# SCH__Atlas_2026-06-21.net
KiCad netlist of a schematic drawn in EasyEDA
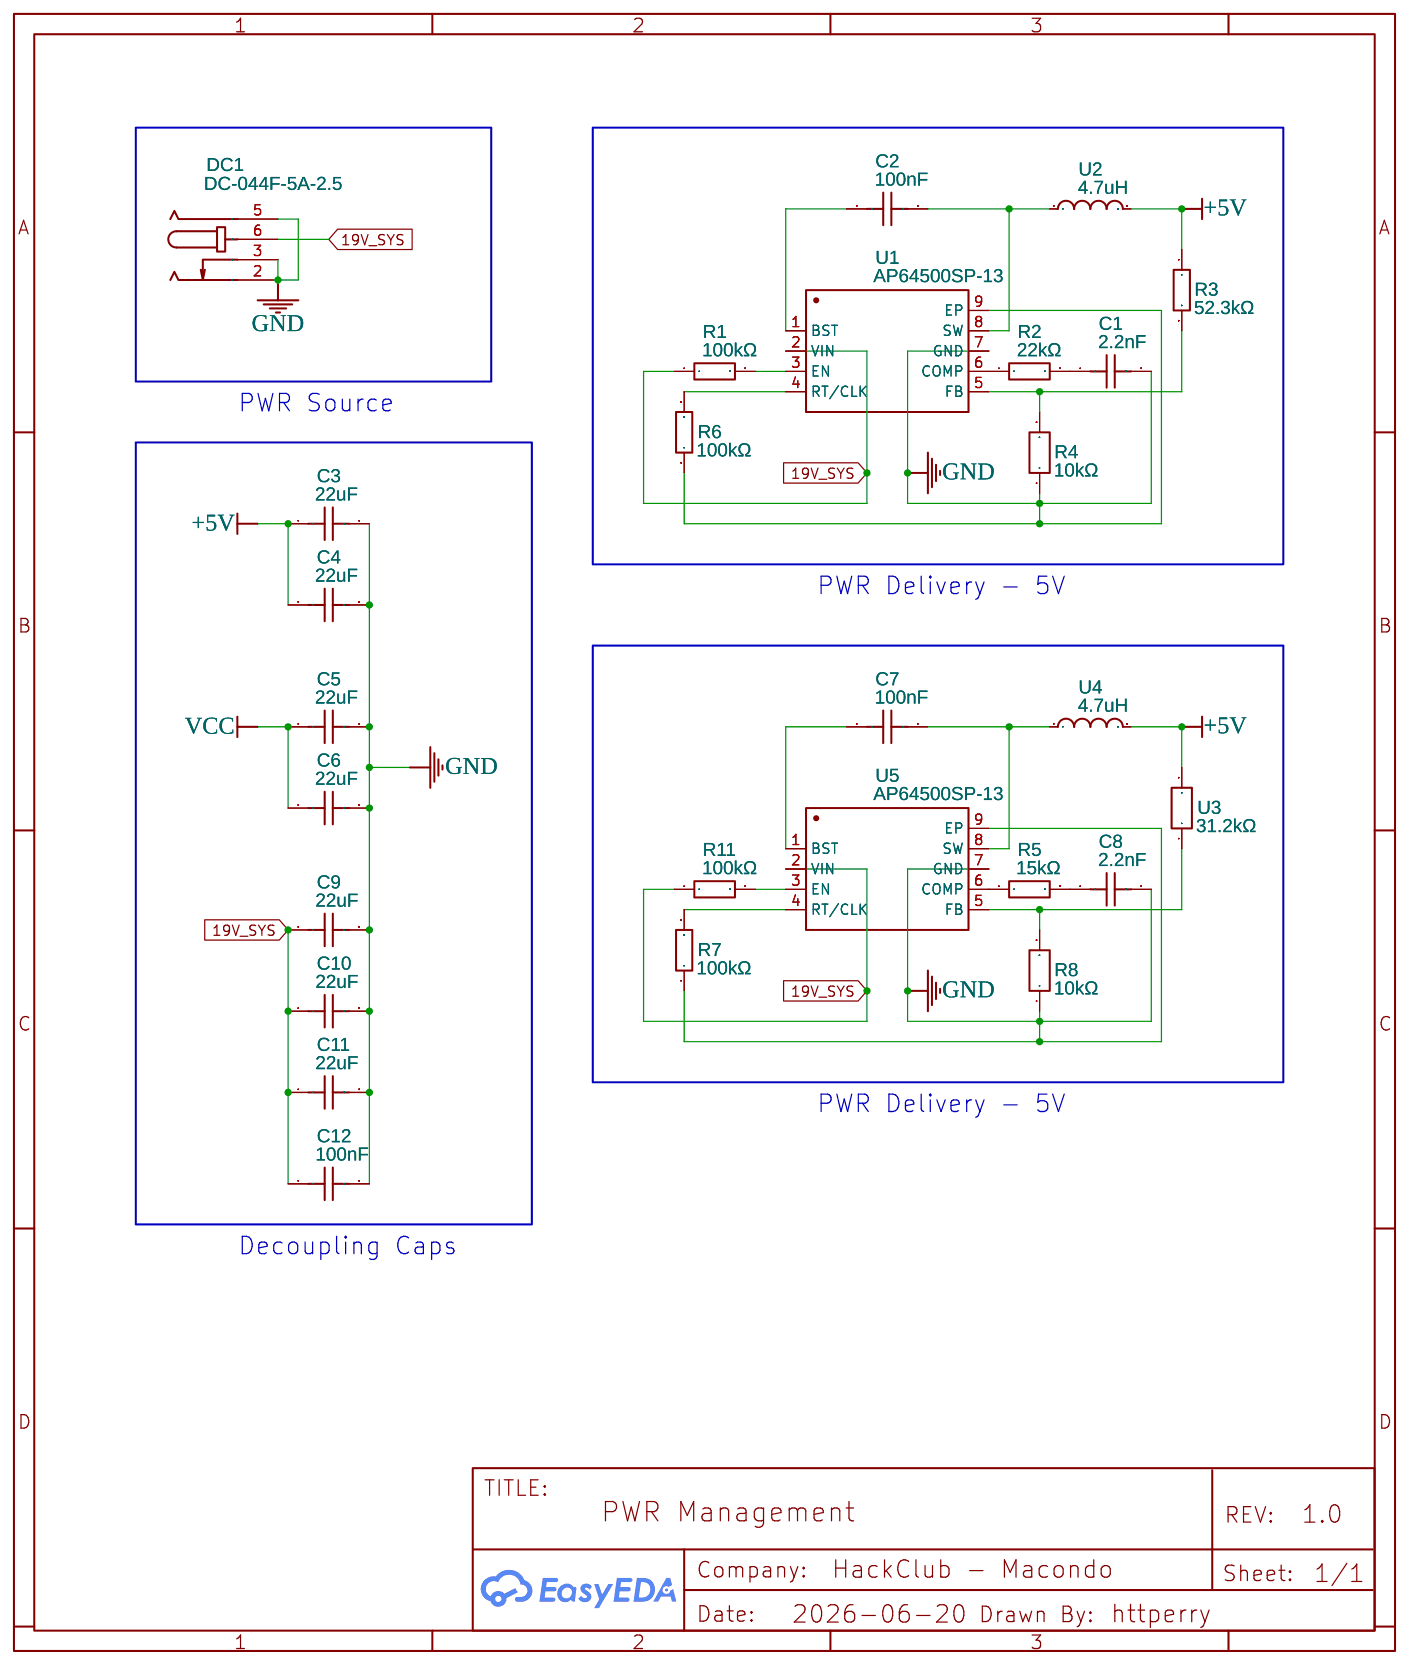
[diagram p0: PWR_Management]
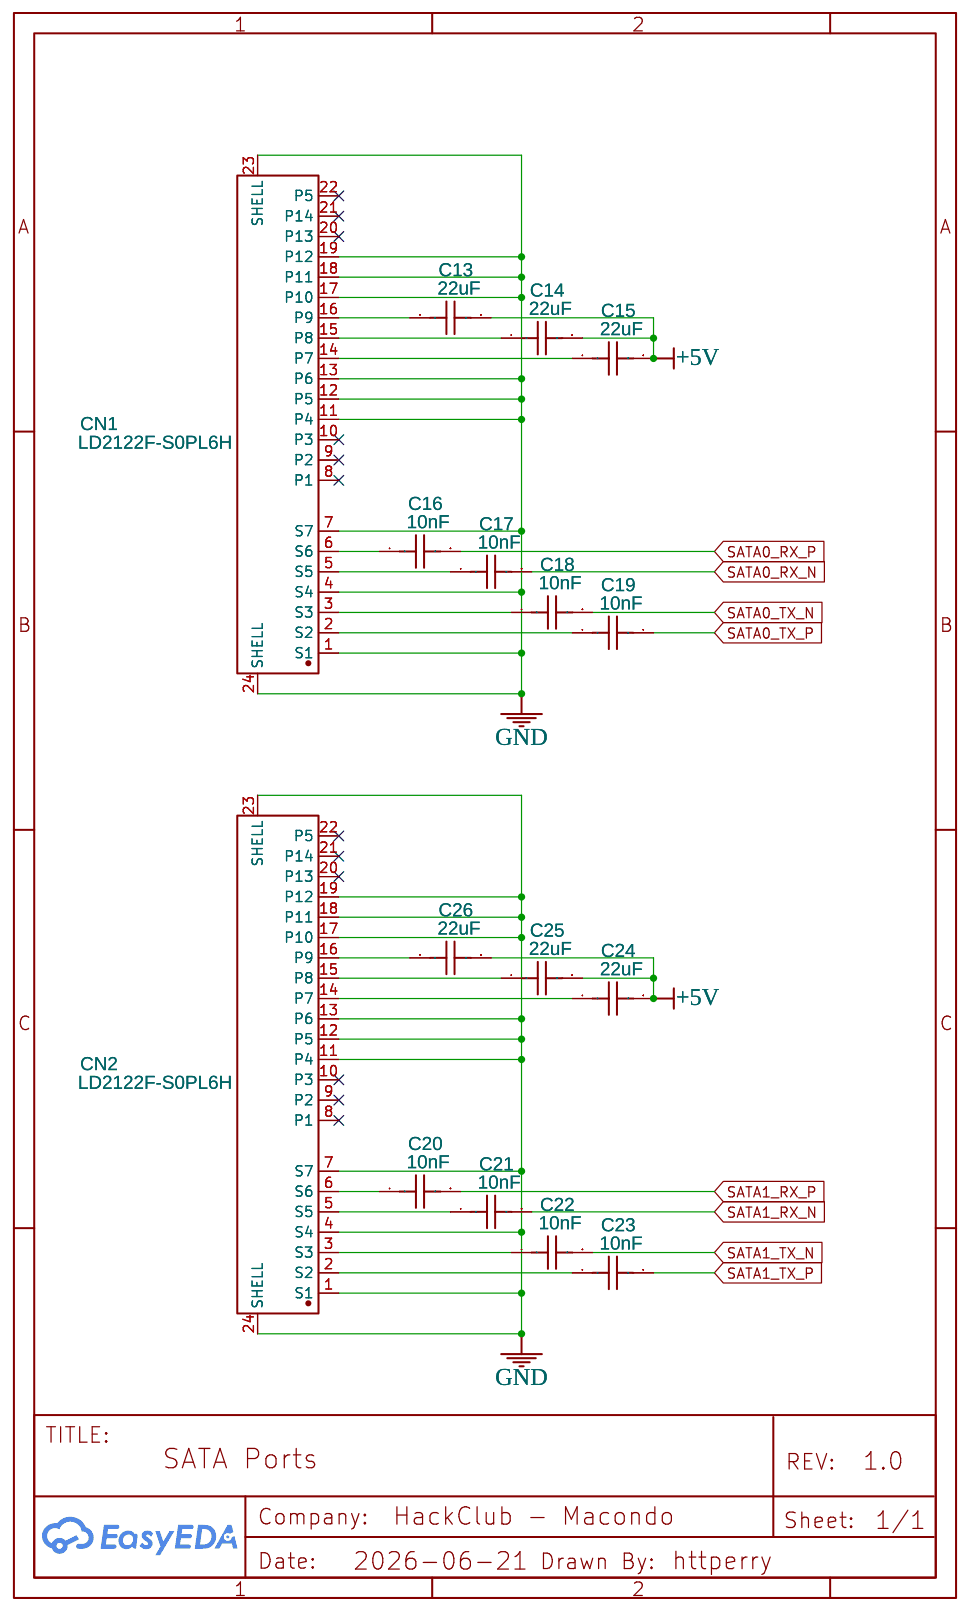
[diagram p1: SATA Ports]

(export (version "E")
  (design (tool "Eeschema 10.0.6"))
  (components
    (comp (ref "C1")
      (value "2.2nF")
      (fields
        (field (name "Manufacturer Part") "FCC0603B222K500CT")
        (field (name "Manufacturer") "FOJAN(富捷)")
      )
      (libsource (lib "") (part "FCC0603B222K500CT"))
    )
    (comp (ref "C2")
      (value "100nF")
      (fields
        (field (name "Manufacturer Part") "GRM188R71H104KA93D")
        (field (name "Manufacturer") "muRata(村田)")
      )
      (libsource (lib "") (part "GRM188R71H104KA93D"))
    )
    (comp (ref "C3")
      (value "22uF")
      (fields
        (field (name "Manufacturer Part") "HGC0603R5226M160NTHJ")
        (field (name "Manufacturer") "Chinocera(华瓷)")
      )
      (libsource (lib "") (part "HGC0603R5226M160NTHJ"))
    )
    (comp (ref "C4")
      (value "22uF")
      (fields
        (field (name "Manufacturer Part") "HGC0603R5226M160NTHJ")
        (field (name "Manufacturer") "Chinocera(华瓷)")
      )
      (libsource (lib "") (part "HGC0603R5226M160NTHJ"))
    )
    (comp (ref "C5")
      (value "22uF")
      (fields
        (field (name "Manufacturer Part") "HGC0603R5226M160NTHJ")
        (field (name "Manufacturer") "Chinocera(华瓷)")
      )
      (libsource (lib "") (part "HGC0603R5226M160NTHJ"))
    )
    (comp (ref "C6")
      (value "22uF")
      (fields
        (field (name "Manufacturer Part") "HGC0603R5226M160NTHJ")
        (field (name "Manufacturer") "Chinocera(华瓷)")
      )
      (libsource (lib "") (part "HGC0603R5226M160NTHJ"))
    )
    (comp (ref "C7")
      (value "100nF")
      (fields
        (field (name "Manufacturer Part") "GRM188R71H104KA93D")
        (field (name "Manufacturer") "muRata(村田)")
      )
      (libsource (lib "") (part "GRM188R71H104KA93D"))
    )
    (comp (ref "C8")
      (value "2.2nF")
      (fields
        (field (name "Manufacturer Part") "FCC0603B222K500CT")
        (field (name "Manufacturer") "FOJAN(富捷)")
      )
      (libsource (lib "") (part "FCC0603B222K500CT"))
    )
    (comp (ref "C9")
      (value "22uF")
      (fields
        (field (name "Manufacturer Part") "KCM55QR71H226KH13K")
        (field (name "Manufacturer") "muRata(村田)")
      )
      (libsource (lib "") (part "KCM55QR71H226KH13K"))
    )
    (comp (ref "C10")
      (value "22uF")
      (fields
        (field (name "Manufacturer Part") "KCM55QR71H226KH13K")
        (field (name "Manufacturer") "muRata(村田)")
      )
      (libsource (lib "") (part "KCM55QR71H226KH13K"))
    )
    (comp (ref "C11")
      (value "22uF")
      (fields
        (field (name "Manufacturer Part") "KCM55QR71H226KH13K")
        (field (name "Manufacturer") "muRata(村田)")
      )
      (libsource (lib "") (part "KCM55QR71H226KH13K"))
    )
    (comp (ref "C12")
      (value "100nF")
      (fields
        (field (name "Manufacturer Part") "GRM188R71H104KA93D")
        (field (name "Manufacturer") "muRata(村田)")
      )
      (libsource (lib "") (part "GRM188R71H104KA93D"))
    )
    (comp (ref "DC1")
      (value "DC-044F-5A-2.5")
      (fields (field (name "Manufacturer") "XKB Connection(中国星坤)"))
      (libsource (lib "") (part "DC-044F-5A-2.5"))
    )
    (comp (ref "R1")
      (value "100kΩ")
      (fields (field (name "Manufacturer Part") "RS-03K1003FT") (field (name "Manufacturer") "FH(风华)"))
      (libsource (lib "") (part "RS-03K1003FT_C115320"))
    )
    (comp (ref "R2")
      (value "22kΩ")
      (fields (field (name "Manufacturer Part") "RS-03K2202FT") (field (name "Manufacturer") "FH(风华)"))
      (libsource (lib "") (part "RS-03K2202FT"))
    )
    (comp (ref "R3")
      (value "52.3kΩ")
      (fields (field (name "Manufacturer Part") "RS-03K5232FT") (field (name "Manufacturer") "FH(风华)"))
      (libsource (lib "") (part "RS-03K5232FT"))
    )
    (comp (ref "R4")
      (value "10kΩ")
      (fields (field (name "Manufacturer Part") "AR03BTS1002") (field (name "Manufacturer") "Viking(光颉)"))
      (libsource (lib "") (part "AR03BTS1002"))
    )
    (comp (ref "R5")
      (value "15kΩ")
      (fields (field (name "Manufacturer Part") "CR0603FA1502G") (field (name "Manufacturer") "LIZ(丽智电子)"))
      (libsource (lib "") (part "CR0603FA1502G"))
    )
    (comp (ref "R6")
      (value "100kΩ")
      (fields (field (name "Manufacturer Part") "RS-03K1003FT") (field (name "Manufacturer") "FH(风华)"))
      (libsource (lib "") (part "RS-03K1003FT_C115320_1"))
    )
    (comp (ref "R7")
      (value "100kΩ")
      (fields (field (name "Manufacturer Part") "RS-03K1003FT") (field (name "Manufacturer") "FH(风华)"))
      (libsource (lib "") (part "RS-03K1003FT_C115320_1"))
    )
    (comp (ref "R8")
      (value "10kΩ")
      (fields (field (name "Manufacturer Part") "AR03BTS1002") (field (name "Manufacturer") "Viking(光颉)"))
      (libsource (lib "") (part "AR03BTS1002"))
    )
    (comp (ref "R11")
      (value "100kΩ")
      (fields (field (name "Manufacturer Part") "RS-03K1003FT") (field (name "Manufacturer") "FH(风华)"))
      (libsource (lib "") (part "RS-03K1003FT_C115320"))
    )
    (comp (ref "U1")
      (value "AP64500SP-13")
      (fields (field (name "Manufacturer") "DIODES(美台)"))
      (libsource (lib "") (part "AP64500SP-13"))
    )
    (comp (ref "U2")
      (value "4.7uH")
      (fields (field (name "Manufacturer Part") "APH0630T4R7M") (field (name "Manufacturer") "APV(爱普微)"))
      (libsource (lib "") (part "APH0630T4R7M"))
    )
    (comp (ref "U3")
      (value "31.2kΩ")
      (fields (field (name "Manufacturer Part") "RT0603DRE0731K2L") (field (name "Manufacturer") "YAGEO(国巨)"))
      (libsource (lib "") (part "RT0603DRE0731K2L"))
    )
    (comp (ref "U4")
      (value "4.7uH")
      (fields (field (name "Manufacturer Part") "APH0630T4R7M") (field (name "Manufacturer") "APV(爱普微)"))
      (libsource (lib "") (part "APH0630T4R7M"))
    )
    (comp (ref "U5")
      (value "AP64500SP-13")
      (fields (field (name "Manufacturer") "DIODES(美台)"))
      (libsource (lib "") (part "AP64500SP-13"))
    )
    (comp (ref "C13")
      (value "22uF")
      (fields
        (field (name "Manufacturer Part") "HGC0603R5226M160NTHJ")
        (field (name "Manufacturer") "Chinocera(华瓷)")
      )
      (libsource (lib "") (part "HGC0603R5226M160NTHJ"))
    )
    (comp (ref "C14")
      (value "22uF")
      (fields
        (field (name "Manufacturer Part") "HGC0603R5226M160NTHJ")
        (field (name "Manufacturer") "Chinocera(华瓷)")
      )
      (libsource (lib "") (part "HGC0603R5226M160NTHJ"))
    )
    (comp (ref "C15")
      (value "22uF")
      (fields
        (field (name "Manufacturer Part") "HGC0603R5226M160NTHJ")
        (field (name "Manufacturer") "Chinocera(华瓷)")
      )
      (libsource (lib "") (part "HGC0603R5226M160NTHJ"))
    )
    (comp (ref "C16")
      (value "10nF")
      (fields
        (field (name "Manufacturer Part") "FCC0402B103K500AT")
        (field (name "Manufacturer") "FOJAN(富捷)")
      )
      (libsource (lib "") (part "FCC0402B103K500AT"))
    )
    (comp (ref "C17")
      (value "10nF")
      (fields
        (field (name "Manufacturer Part") "FCC0402B103K500AT")
        (field (name "Manufacturer") "FOJAN(富捷)")
      )
      (libsource (lib "") (part "FCC0402B103K500AT"))
    )
    (comp (ref "C18")
      (value "10nF")
      (fields
        (field (name "Manufacturer Part") "FCC0402B103K500AT")
        (field (name "Manufacturer") "FOJAN(富捷)")
      )
      (libsource (lib "") (part "FCC0402B103K500AT"))
    )
    (comp (ref "C19")
      (value "10nF")
      (fields
        (field (name "Manufacturer Part") "FCC0402B103K500AT")
        (field (name "Manufacturer") "FOJAN(富捷)")
      )
      (libsource (lib "") (part "FCC0402B103K500AT"))
    )
    (comp (ref "C20")
      (value "10nF")
      (fields
        (field (name "Manufacturer Part") "FCC0402B103K500AT")
        (field (name "Manufacturer") "FOJAN(富捷)")
      )
      (libsource (lib "") (part "FCC0402B103K500AT"))
    )
    (comp (ref "C21")
      (value "10nF")
      (fields
        (field (name "Manufacturer Part") "FCC0402B103K500AT")
        (field (name "Manufacturer") "FOJAN(富捷)")
      )
      (libsource (lib "") (part "FCC0402B103K500AT"))
    )
    (comp (ref "C22")
      (value "10nF")
      (fields
        (field (name "Manufacturer Part") "FCC0402B103K500AT")
        (field (name "Manufacturer") "FOJAN(富捷)")
      )
      (libsource (lib "") (part "FCC0402B103K500AT"))
    )
    (comp (ref "C23")
      (value "10nF")
      (fields
        (field (name "Manufacturer Part") "FCC0402B103K500AT")
        (field (name "Manufacturer") "FOJAN(富捷)")
      )
      (libsource (lib "") (part "FCC0402B103K500AT"))
    )
    (comp (ref "C24")
      (value "22uF")
      (fields
        (field (name "Manufacturer Part") "HGC0603R5226M160NTHJ")
        (field (name "Manufacturer") "Chinocera(华瓷)")
      )
      (libsource (lib "") (part "HGC0603R5226M160NTHJ"))
    )
    (comp (ref "C25")
      (value "22uF")
      (fields
        (field (name "Manufacturer Part") "HGC0603R5226M160NTHJ")
        (field (name "Manufacturer") "Chinocera(华瓷)")
      )
      (libsource (lib "") (part "HGC0603R5226M160NTHJ"))
    )
    (comp (ref "C26")
      (value "22uF")
      (fields
        (field (name "Manufacturer Part") "HGC0603R5226M160NTHJ")
        (field (name "Manufacturer") "Chinocera(华瓷)")
      )
      (libsource (lib "") (part "HGC0603R5226M160NTHJ"))
    )
    (comp (ref "CN1")
      (value "LD2122F-S0PL6H")
      (fields (field (name "Manufacturer") "FOXCONN(富士康)"))
      (libsource (lib "") (part "LD2122F-S0PL6H"))
    )
    (comp (ref "CN2")
      (value "LD2122F-S0PL6H")
      (fields (field (name "Manufacturer") "FOXCONN(富士康)"))
      (libsource (lib "") (part "LD2122F-S0PL6H"))
    )
  )
  (nets
    (net (code "1") (name "+5V") (class "Default")
      (node (ref "C13") (pin "2") (pinfunction "2_2") (pintype "unspecified"))
      (node (ref "C14") (pin "2") (pinfunction "2_2") (pintype "unspecified"))
      (node (ref "C15") (pin "2") (pinfunction "2_2") (pintype "unspecified"))
      (node (ref "C24") (pin "2") (pinfunction "2_2") (pintype "unspecified"))
      (node (ref "C25") (pin "2") (pinfunction "2_2") (pintype "unspecified"))
      (node (ref "C26") (pin "2") (pinfunction "2_2") (pintype "unspecified"))
      (node (ref "C3") (pin "1") (pinfunction "1_1") (pintype "unspecified"))
      (node (ref "C4") (pin "1") (pinfunction "1_1") (pintype "unspecified"))
      (node (ref "R3") (pin "1") (pinfunction "1_1") (pintype "unspecified"))
      (node (ref "U2") (pin "2") (pinfunction "2_2") (pintype "unspecified"))
      (node (ref "U3") (pin "2") (pinfunction "2_2") (pintype "unspecified"))
      (node (ref "U4") (pin "2") (pinfunction "2_2") (pintype "unspecified"))
    )
    (net (code "2") (name "19V_SYS") (class "Default")
      (node (ref "C10") (pin "1") (pinfunction "1_1") (pintype "unspecified"))
      (node (ref "C11") (pin "1") (pinfunction "1_1") (pintype "unspecified"))
      (node (ref "C12") (pin "1") (pinfunction "1_1") (pintype "unspecified"))
      (node (ref "C9") (pin "1") (pinfunction "1_1") (pintype "unspecified"))
      (node (ref "DC1") (pin "6") (pinfunction "6_6") (pintype "unspecified"))
      (node (ref "R1") (pin "1") (pinfunction "1_1") (pintype "unspecified"))
      (node (ref "R11") (pin "1") (pinfunction "1_1") (pintype "unspecified"))
      (node (ref "U1") (pin "2") (pinfunction "VIN_2") (pintype "unspecified"))
      (node (ref "U5") (pin "2") (pinfunction "VIN_2") (pintype "unspecified"))
    )
    (net (code "3") (name "GND") (class "Default")
      (node (ref "C1") (pin "2") (pinfunction "2_2") (pintype "unspecified"))
      (node (ref "C10") (pin "2") (pinfunction "2_2") (pintype "unspecified"))
      (node (ref "C11") (pin "2") (pinfunction "2_2") (pintype "unspecified"))
      (node (ref "C12") (pin "2") (pinfunction "2_2") (pintype "unspecified"))
      (node (ref "C3") (pin "2") (pinfunction "2_2") (pintype "unspecified"))
      (node (ref "C4") (pin "2") (pinfunction "2_2") (pintype "unspecified"))
      (node (ref "C5") (pin "2") (pinfunction "2_2") (pintype "unspecified"))
      (node (ref "C6") (pin "2") (pinfunction "2_2") (pintype "unspecified"))
      (node (ref "C8") (pin "2") (pinfunction "2_2") (pintype "unspecified"))
      (node (ref "C9") (pin "2") (pinfunction "2_2") (pintype "unspecified"))
      (node (ref "CN1") (pin "1") (pinfunction "S1_1") (pintype "unspecified"))
      (node (ref "CN1") (pin "11") (pinfunction "P4_11") (pintype "unspecified"))
      (node (ref "CN1") (pin "12") (pinfunction "P5_12") (pintype "unspecified"))
      (node (ref "CN1") (pin "13") (pinfunction "P6_13") (pintype "unspecified"))
      (node (ref "CN1") (pin "17") (pinfunction "P10_17") (pintype "unspecified"))
      (node (ref "CN1") (pin "18") (pinfunction "P11_18") (pintype "unspecified"))
      (node (ref "CN1") (pin "19") (pinfunction "P12_19") (pintype "unspecified"))
      (node (ref "CN1") (pin "23") (pinfunction "SHELL_23") (pintype "unspecified"))
      (node (ref "CN1") (pin "24") (pinfunction "SHELL_24") (pintype "unspecified"))
      (node (ref "CN1") (pin "4") (pinfunction "S4_4") (pintype "unspecified"))
      (node (ref "CN1") (pin "7") (pinfunction "S7_7") (pintype "unspecified"))
      (node (ref "CN2") (pin "1") (pinfunction "S1_1") (pintype "unspecified"))
      (node (ref "CN2") (pin "11") (pinfunction "P4_11") (pintype "unspecified"))
      (node (ref "CN2") (pin "12") (pinfunction "P5_12") (pintype "unspecified"))
      (node (ref "CN2") (pin "13") (pinfunction "P6_13") (pintype "unspecified"))
      (node (ref "CN2") (pin "17") (pinfunction "P10_17") (pintype "unspecified"))
      (node (ref "CN2") (pin "18") (pinfunction "P11_18") (pintype "unspecified"))
      (node (ref "CN2") (pin "19") (pinfunction "P12_19") (pintype "unspecified"))
      (node (ref "CN2") (pin "23") (pinfunction "SHELL_23") (pintype "unspecified"))
      (node (ref "CN2") (pin "24") (pinfunction "SHELL_24") (pintype "unspecified"))
      (node (ref "CN2") (pin "4") (pinfunction "S4_4") (pintype "unspecified"))
      (node (ref "CN2") (pin "7") (pinfunction "S7_7") (pintype "unspecified"))
      (node (ref "DC1") (pin "2") (pinfunction "2_2") (pintype "unspecified"))
      (node (ref "DC1") (pin "3") (pinfunction "3_3") (pintype "unspecified"))
      (node (ref "DC1") (pin "5") (pinfunction "5_5") (pintype "unspecified"))
      (node (ref "R4") (pin "1") (pinfunction "1_1") (pintype "unspecified"))
      (node (ref "R6") (pin "1") (pinfunction "1_1") (pintype "unspecified"))
      (node (ref "R7") (pin "1") (pinfunction "1_1") (pintype "unspecified"))
      (node (ref "R8") (pin "1") (pinfunction "1_1") (pintype "unspecified"))
      (node (ref "U1") (pin "7") (pinfunction "GND_7") (pintype "unspecified"))
      (node (ref "U1") (pin "9") (pinfunction "EP_9") (pintype "unspecified"))
      (node (ref "U5") (pin "7") (pinfunction "GND_7") (pintype "unspecified"))
      (node (ref "U5") (pin "9") (pinfunction "EP_9") (pintype "unspecified"))
    )
    (net (code "4") (name "Net-(C1-Pad1)") (class "Default")
      (node (ref "C1") (pin "1") (pinfunction "1_1") (pintype "unspecified"))
      (node (ref "R2") (pin "2") (pinfunction "2_2") (pintype "unspecified"))
    )
    (net (code "5") (name "Net-(C8-Pad1)") (class "Default")
      (node (ref "C8") (pin "1") (pinfunction "1_1") (pintype "unspecified"))
      (node (ref "R5") (pin "2") (pinfunction "2_2") (pintype "input"))
    )
    (net (code "6") (name "Net-(CN1-P7)") (class "Default")
      (node (ref "C15") (pin "1") (pinfunction "1_1") (pintype "unspecified"))
      (node (ref "CN1") (pin "14") (pinfunction "P7_14") (pintype "unspecified"))
    )
    (net (code "7") (name "Net-(CN1-P8)") (class "Default")
      (node (ref "C14") (pin "1") (pinfunction "1_1") (pintype "unspecified"))
      (node (ref "CN1") (pin "15") (pinfunction "P8_15") (pintype "unspecified"))
    )
    (net (code "8") (name "Net-(CN1-P9)") (class "Default")
      (node (ref "C13") (pin "1") (pinfunction "1_1") (pintype "unspecified"))
      (node (ref "CN1") (pin "16") (pinfunction "P9_16") (pintype "unspecified"))
    )
    (net (code "9") (name "Net-(CN1-S2)") (class "Default")
      (node (ref "C19") (pin "1") (pinfunction "1_1") (pintype "unspecified"))
      (node (ref "CN1") (pin "2") (pinfunction "S2_2") (pintype "unspecified"))
    )
    (net (code "10") (name "Net-(CN1-S3)") (class "Default")
      (node (ref "C18") (pin "1") (pinfunction "1_1") (pintype "unspecified"))
      (node (ref "CN1") (pin "3") (pinfunction "S3_3") (pintype "unspecified"))
    )
    (net (code "11") (name "Net-(CN1-S5)") (class "Default")
      (node (ref "C17") (pin "1") (pinfunction "1_1") (pintype "unspecified"))
      (node (ref "CN1") (pin "5") (pinfunction "S5_5") (pintype "unspecified"))
    )
    (net (code "12") (name "Net-(CN1-S6)") (class "Default")
      (node (ref "C16") (pin "1") (pinfunction "1_1") (pintype "unspecified"))
      (node (ref "CN1") (pin "6") (pinfunction "S6_6") (pintype "unspecified"))
    )
    (net (code "13") (name "Net-(CN2-P7)") (class "Default")
      (node (ref "C24") (pin "1") (pinfunction "1_1") (pintype "unspecified"))
      (node (ref "CN2") (pin "14") (pinfunction "P7_14") (pintype "unspecified"))
    )
    (net (code "14") (name "Net-(CN2-P8)") (class "Default")
      (node (ref "C25") (pin "1") (pinfunction "1_1") (pintype "unspecified"))
      (node (ref "CN2") (pin "15") (pinfunction "P8_15") (pintype "unspecified"))
    )
    (net (code "15") (name "Net-(CN2-P9)") (class "Default")
      (node (ref "C26") (pin "1") (pinfunction "1_1") (pintype "unspecified"))
      (node (ref "CN2") (pin "16") (pinfunction "P9_16") (pintype "unspecified"))
    )
    (net (code "16") (name "Net-(CN2-S2)") (class "Default")
      (node (ref "C23") (pin "1") (pinfunction "1_1") (pintype "unspecified"))
      (node (ref "CN2") (pin "2") (pinfunction "S2_2") (pintype "unspecified"))
    )
    (net (code "17") (name "Net-(CN2-S3)") (class "Default")
      (node (ref "C22") (pin "1") (pinfunction "1_1") (pintype "unspecified"))
      (node (ref "CN2") (pin "3") (pinfunction "S3_3") (pintype "unspecified"))
    )
    (net (code "18") (name "Net-(CN2-S5)") (class "Default")
      (node (ref "C21") (pin "1") (pinfunction "1_1") (pintype "unspecified"))
      (node (ref "CN2") (pin "5") (pinfunction "S5_5") (pintype "unspecified"))
    )
    (net (code "19") (name "Net-(CN2-S6)") (class "Default")
      (node (ref "C20") (pin "1") (pinfunction "1_1") (pintype "unspecified"))
      (node (ref "CN2") (pin "6") (pinfunction "S6_6") (pintype "unspecified"))
    )
    (net (code "20") (name "Net-(U1-BST)") (class "Default")
      (node (ref "C2") (pin "1") (pinfunction "1_1") (pintype "unspecified"))
      (node (ref "U1") (pin "1") (pinfunction "BST_1") (pintype "unspecified"))
    )
    (net (code "21") (name "Net-(U1-COMP)") (class "Default")
      (node (ref "R2") (pin "1") (pinfunction "1_1") (pintype "unspecified"))
      (node (ref "U1") (pin "6") (pinfunction "COMP_6") (pintype "unspecified"))
    )
    (net (code "22") (name "Net-(U1-EN)") (class "Default")
      (node (ref "R1") (pin "2") (pinfunction "2_2") (pintype "unspecified"))
      (node (ref "U1") (pin "3") (pinfunction "EN_3") (pintype "unspecified"))
    )
    (net (code "23") (name "Net-(U1-FB)") (class "Default")
      (node (ref "R3") (pin "2") (pinfunction "2_2") (pintype "unspecified"))
      (node (ref "R4") (pin "2") (pinfunction "2_2") (pintype "unspecified"))
      (node (ref "U1") (pin "5") (pinfunction "FB_5") (pintype "unspecified"))
    )
    (net (code "24") (name "Net-(U1-RT{slash}CLK)") (class "Default")
      (node (ref "R6") (pin "2") (pinfunction "2_2") (pintype "unspecified"))
      (node (ref "U1") (pin "4") (pinfunction "RT/CLK_4") (pintype "unspecified"))
    )
    (net (code "25") (name "Net-(U1-SW)") (class "Default")
      (node (ref "C2") (pin "2") (pinfunction "2_2") (pintype "unspecified"))
      (node (ref "U1") (pin "8") (pinfunction "SW_8") (pintype "unspecified"))
      (node (ref "U2") (pin "1") (pinfunction "1_1") (pintype "unspecified"))
    )
    (net (code "26") (name "Net-(U5-BST)") (class "Default")
      (node (ref "C7") (pin "1") (pinfunction "1_1") (pintype "unspecified"))
      (node (ref "U5") (pin "1") (pinfunction "BST_1") (pintype "unspecified"))
    )
    (net (code "27") (name "Net-(U5-COMP)") (class "Default")
      (node (ref "R5") (pin "1") (pinfunction "1_1") (pintype "input"))
      (node (ref "U5") (pin "6") (pinfunction "COMP_6") (pintype "unspecified"))
    )
    (net (code "28") (name "Net-(U5-EN)") (class "Default")
      (node (ref "R11") (pin "2") (pinfunction "2_2") (pintype "unspecified"))
      (node (ref "U5") (pin "3") (pinfunction "EN_3") (pintype "unspecified"))
    )
    (net (code "29") (name "Net-(U5-FB)") (class "Default")
      (node (ref "R8") (pin "2") (pinfunction "2_2") (pintype "unspecified"))
      (node (ref "U3") (pin "1") (pinfunction "1_1") (pintype "unspecified"))
      (node (ref "U5") (pin "5") (pinfunction "FB_5") (pintype "unspecified"))
    )
    (net (code "30") (name "Net-(U5-RT{slash}CLK)") (class "Default")
      (node (ref "R7") (pin "2") (pinfunction "2_2") (pintype "unspecified"))
      (node (ref "U5") (pin "4") (pinfunction "RT/CLK_4") (pintype "unspecified"))
    )
    (net (code "31") (name "Net-(U5-SW)") (class "Default")
      (node (ref "C7") (pin "2") (pinfunction "2_2") (pintype "unspecified"))
      (node (ref "U4") (pin "1") (pinfunction "1_1") (pintype "unspecified"))
      (node (ref "U5") (pin "8") (pinfunction "SW_8") (pintype "unspecified"))
    )
    (net (code "32") (name "SATA0_RX_N") (class "Default")
      (node (ref "C17") (pin "2") (pinfunction "2_2") (pintype "unspecified"))
    )
    (net (code "33") (name "SATA0_RX_P") (class "Default")
      (node (ref "C16") (pin "2") (pinfunction "2_2") (pintype "unspecified"))
    )
    (net (code "34") (name "SATA0_TX_N") (class "Default")
      (node (ref "C18") (pin "2") (pinfunction "2_2") (pintype "unspecified"))
    )
    (net (code "35") (name "SATA0_TX_P") (class "Default")
      (node (ref "C19") (pin "2") (pinfunction "2_2") (pintype "unspecified"))
    )
    (net (code "36") (name "SATA1_RX_N") (class "Default")
      (node (ref "C21") (pin "2") (pinfunction "2_2") (pintype "unspecified"))
    )
    (net (code "37") (name "SATA1_RX_P") (class "Default")
      (node (ref "C20") (pin "2") (pinfunction "2_2") (pintype "unspecified"))
    )
    (net (code "38") (name "SATA1_TX_N") (class "Default")
      (node (ref "C22") (pin "2") (pinfunction "2_2") (pintype "unspecified"))
    )
    (net (code "39") (name "SATA1_TX_P") (class "Default")
      (node (ref "C23") (pin "2") (pinfunction "2_2") (pintype "unspecified"))
    )
    (net (code "40") (name "VCC") (class "Default")
      (node (ref "C5") (pin "1") (pinfunction "1_1") (pintype "unspecified"))
      (node (ref "C6") (pin "1") (pinfunction "1_1") (pintype "unspecified"))
    )
    (net (code "41") (name "unconnected-(CN1-P1-Pad8)") (class "Default")
      (node (ref "CN1") (pin "8") (pinfunction "P1_8") (pintype "unspecified+no_connect"))
    )
    (net (code "42") (name "unconnected-(CN1-P2-Pad9)") (class "Default")
      (node (ref "CN1") (pin "9") (pinfunction "P2_9") (pintype "unspecified+no_connect"))
    )
    (net (code "43") (name "unconnected-(CN1-P3-Pad10)") (class "Default")
      (node (ref "CN1") (pin "10") (pinfunction "P3_10") (pintype "unspecified+no_connect"))
    )
    (net (code "44") (name "unconnected-(CN1-P5-Pad22)") (class "Default")
      (node (ref "CN1") (pin "22") (pinfunction "P5_22") (pintype "unspecified+no_connect"))
    )
    (net (code "45") (name "unconnected-(CN1-P13-Pad20)") (class "Default")
      (node (ref "CN1") (pin "20") (pinfunction "P13_20") (pintype "unspecified+no_connect"))
    )
    (net (code "46") (name "unconnected-(CN1-P14-Pad21)") (class "Default")
      (node (ref "CN1") (pin "21") (pinfunction "P14_21") (pintype "unspecified+no_connect"))
    )
    (net (code "47") (name "unconnected-(CN2-P1-Pad8)") (class "Default")
      (node (ref "CN2") (pin "8") (pinfunction "P1_8") (pintype "unspecified+no_connect"))
    )
    (net (code "48") (name "unconnected-(CN2-P2-Pad9)") (class "Default")
      (node (ref "CN2") (pin "9") (pinfunction "P2_9") (pintype "unspecified+no_connect"))
    )
    (net (code "49") (name "unconnected-(CN2-P3-Pad10)") (class "Default")
      (node (ref "CN2") (pin "10") (pinfunction "P3_10") (pintype "unspecified+no_connect"))
    )
    (net (code "50") (name "unconnected-(CN2-P5-Pad22)") (class "Default")
      (node (ref "CN2") (pin "22") (pinfunction "P5_22") (pintype "unspecified+no_connect"))
    )
    (net (code "51") (name "unconnected-(CN2-P13-Pad20)") (class "Default")
      (node (ref "CN2") (pin "20") (pinfunction "P13_20") (pintype "unspecified+no_connect"))
    )
    (net (code "52") (name "unconnected-(CN2-P14-Pad21)") (class "Default")
      (node (ref "CN2") (pin "21") (pinfunction "P14_21") (pintype "unspecified+no_connect"))
    )
  )
)
